# Filter_Capacitors_-_ADC_Sensor.net
KiCad netlist of a schematic drawn in Altium Designer
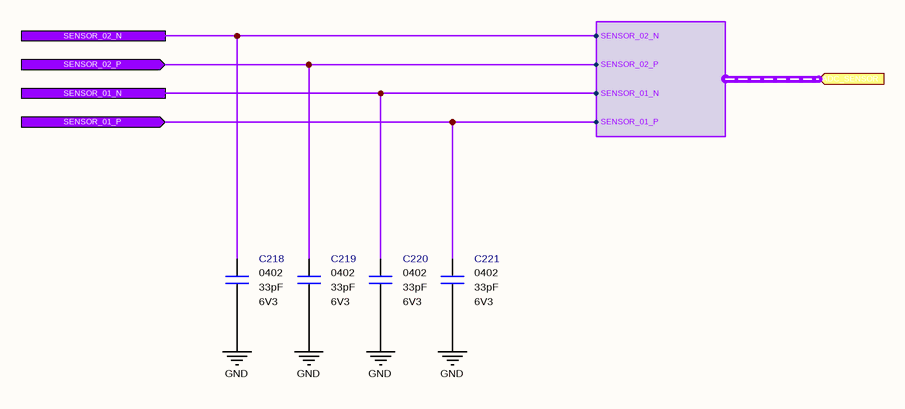
[diagram p0: Filter Capacitors - ADC Sensor.SchDoc]

(export (version "E")
  (design (tool "Eeschema 10.0.6"))
  (components
    (comp (ref "C218")
      (value "33pF")
      (footprint "CAPACITOR_0402")
      (description "Capacitor - 33pF [0402] (Ceramic)")
      (fields
        (field (name "TOLERANCE") "10%")
        (field (name "CASE") "0402")
        (field (name "VOLTAGE") "6V3")
        (field (name "MANUFACTURER PART NUMBER") "C0402C330J9RACAUTO")
      )
      (libsource (lib "Ovoo_Library") (part "Capacitor - 33pF [0402-6V3]"))
    )
    (comp (ref "C219")
      (value "33pF")
      (footprint "CAPACITOR_0402")
      (description "Capacitor - 33pF [0402] (Ceramic)")
      (fields
        (field (name "TOLERANCE") "10%")
        (field (name "CASE") "0402")
        (field (name "VOLTAGE") "6V3")
        (field (name "MANUFACTURER PART NUMBER") "C0402C330J9RACAUTO")
      )
      (libsource (lib "Ovoo_Library") (part "Capacitor - 33pF [0402-6V3]"))
    )
    (comp (ref "C220")
      (value "33pF")
      (footprint "CAPACITOR_0402")
      (description "Capacitor - 33pF [0402] (Ceramic)")
      (fields
        (field (name "TOLERANCE") "10%")
        (field (name "CASE") "0402")
        (field (name "VOLTAGE") "6V3")
        (field (name "MANUFACTURER PART NUMBER") "C0402C330J9RACAUTO")
      )
      (libsource (lib "Ovoo_Library") (part "Capacitor - 33pF [0402-6V3]"))
    )
    (comp (ref "C221")
      (value "33pF")
      (footprint "CAPACITOR_0402")
      (description "Capacitor - 33pF [0402] (Ceramic)")
      (fields
        (field (name "TOLERANCE") "10%")
        (field (name "CASE") "0402")
        (field (name "VOLTAGE") "6V3")
        (field (name "MANUFACTURER PART NUMBER") "C0402C330J9RACAUTO")
      )
      (libsource (lib "Ovoo_Library") (part "Capacitor - 33pF [0402-6V3]"))
    )
  )
  (nets
    (net (code "2") (name "/SENSOR_01_N") (class "Default")
      (node (ref "C220") (pin "2") (pinfunction "2_2") (pintype "passive"))
    )
    (net (code "3") (name "/SENSOR_01_P") (class "Default")
      (node (ref "C221") (pin "2") (pinfunction "2_2") (pintype "passive"))
    )
    (net (code "4") (name "/SENSOR_02_N") (class "Default")
      (node (ref "C218") (pin "2") (pinfunction "2_2") (pintype "passive"))
    )
    (net (code "5") (name "/SENSOR_02_P") (class "Default")
      (node (ref "C219") (pin "2") (pinfunction "2_2") (pintype "passive"))
    )
    (net (code "7") (name "GND") (class "Default")
      (node (ref "C218") (pin "1") (pinfunction "1_1") (pintype "passive"))
      (node (ref "C219") (pin "1") (pinfunction "1_1") (pintype "passive"))
      (node (ref "C220") (pin "1") (pinfunction "1_1") (pintype "passive"))
      (node (ref "C221") (pin "1") (pinfunction "1_1") (pintype "passive"))
    )
  )
)
